# SCH_ESP32-v1_2025-11-17.net
KiCad netlist of a schematic drawn in EasyEDA
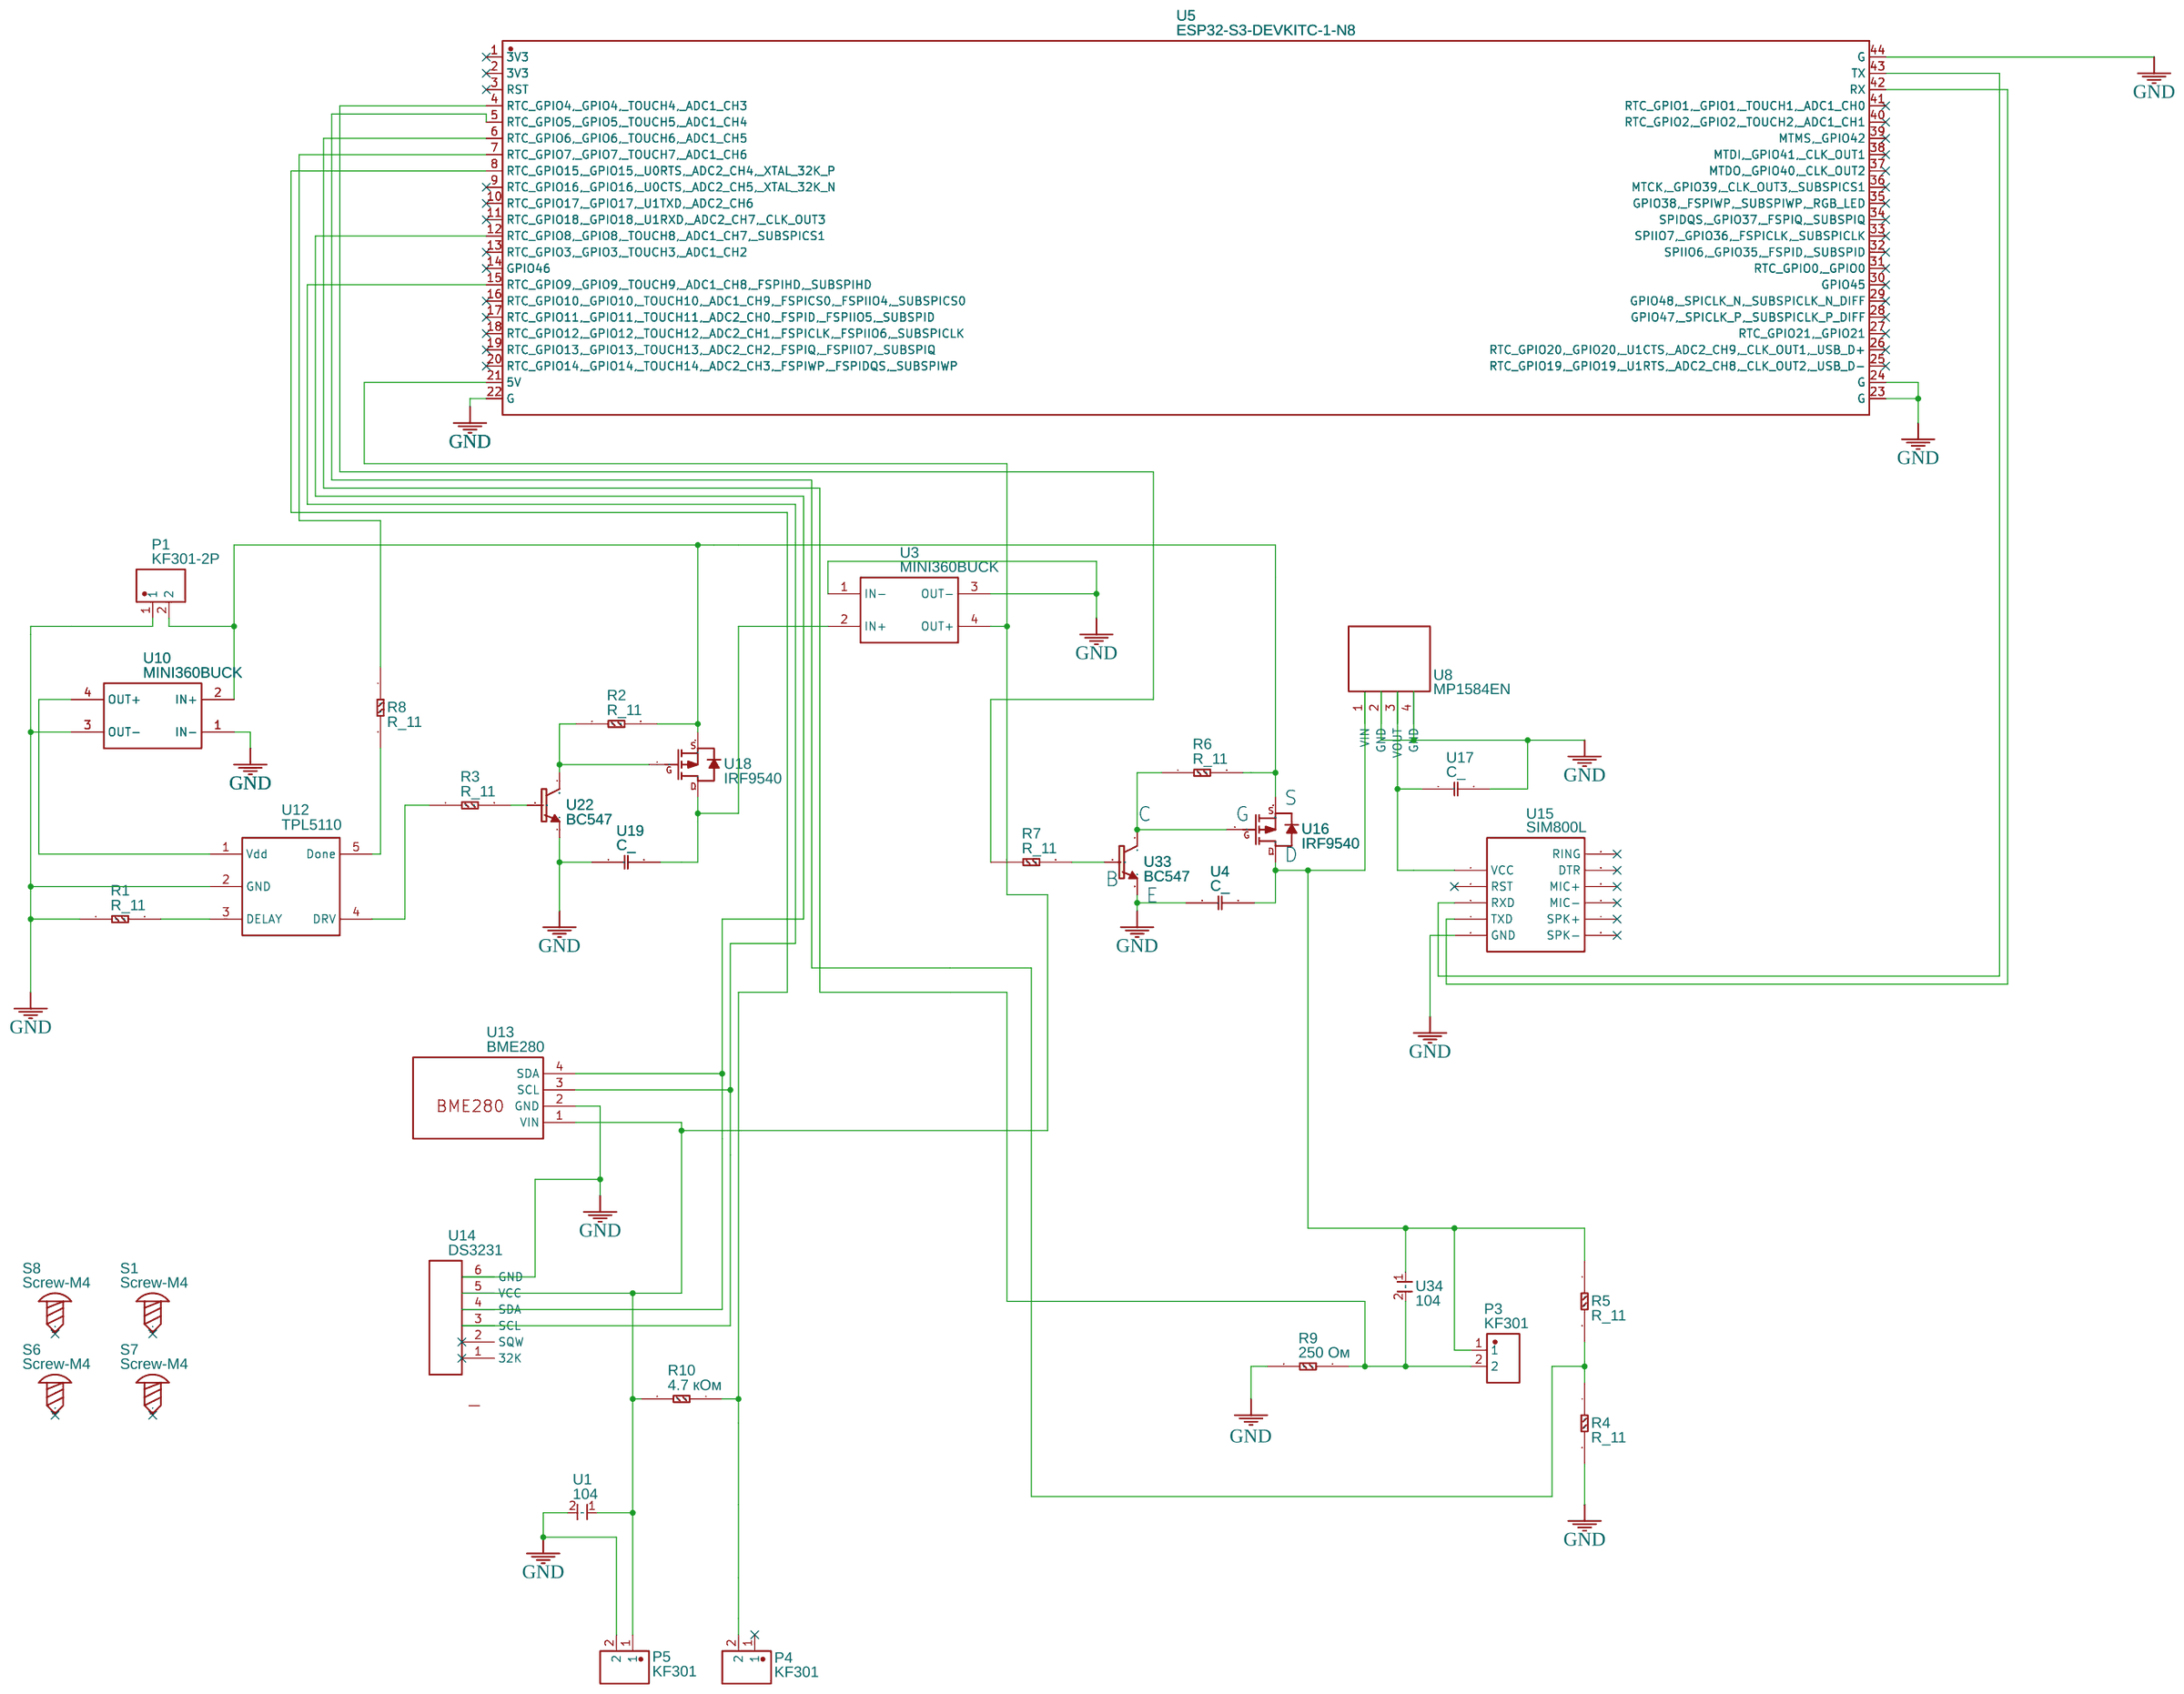
[diagram p0: schematic sheet]

(export (version "E")
  (design (tool "Eeschema 10.0.6"))
  (components
    (comp (ref "P1")
      (value "KF301-2P")
      (fields (field (name "Manufacturer Part") "KF301-2P接线端子"))
      (libsource (lib "") (part "KF301-2P VCC Y GND_1"))
    )
    (comp (ref "P3")
      (value "KF301")
      (fields (field (name "Manufacturer Part") "KF301-2P接线端子"))
      (libsource (lib "") (part "KF301-2P VCC Y GND_2"))
    )
    (comp (ref "P4")
      (value "KF301")
      (fields (field (name "Manufacturer Part") "KF301-2P接线端子"))
      (libsource (lib "") (part "KF301-2P VCC Y GND"))
    )
    (comp (ref "P5")
      (value "KF301")
      (fields (field (name "Manufacturer Part") "KF301-2P接线端子"))
      (libsource (lib "") (part "KF301-2P VCC Y GND"))
    )
    (comp (ref "R1") (value "R_11") (libsource (lib "") (part "R_")))
    (comp (ref "R2") (value "R_11") (libsource (lib "") (part "R_")))
    (comp (ref "R3") (value "R_11") (libsource (lib "") (part "R_")))
    (comp (ref "R4") (value "R_11") (libsource (lib "") (part "R__2")))
    (comp (ref "R5") (value "R_11") (libsource (lib "") (part "R__2")))
    (comp (ref "R6") (value "R_11") (libsource (lib "") (part "R_")))
    (comp (ref "R7") (value "R_11") (libsource (lib "") (part "R_")))
    (comp (ref "R8") (value "R_11") (libsource (lib "") (part "R__2")))
    (comp (ref "R9") (value "250 Ом") (libsource (lib "") (part "R__1")))
    (comp (ref "R10") (value "4.7 кОм") (libsource (lib "") (part "R__1")))
    (comp (ref "S1") (value "Screw-M4") (libsource (lib "") (part "Screw-M4")))
    (comp (ref "S6") (value "Screw-M4") (libsource (lib "") (part "Screw-M4")))
    (comp (ref "S7") (value "Screw-M4") (libsource (lib "") (part "Screw-M4")))
    (comp (ref "S8") (value "Screw-M4") (libsource (lib "") (part "Screw-M4")))
    (comp (ref "U1")
      (value "104")
      (fields (field (name "Manufacturer") "Fe"))
      (libsource (lib "") (part "104"))
    )
    (comp (ref "U3")
      (value "MINI360BUCK")
      (fields (field (name "Manufacturer Part") "Mini360"))
      (libsource (lib "") (part "MINI360BUCK_1"))
    )
    (comp (ref "U4") (value "C_") (libsource (lib "") (part "C_")))
    (comp (ref "U5")
      (value "ESP32-S3-DEVKITC-1-N8")
      (fields (field (name "Manufacturer") "ESPRESSIF(乐鑫)"))
      (libsource (lib "") (part "ESP32-S3-DEVKITC-1-N8"))
    )
    (comp (ref "U8") (value "MP1584EN") (libsource (lib "") (part "MP1584EN")))
    (comp (ref "U10")
      (value "MINI360BUCK")
      (fields (field (name "Manufacturer Part") "Mini360"))
      (libsource (lib "") (part "MINI360BUCK"))
    )
    (comp (ref "U12")
      (value "TPL5110")
      (fields (field (name "Manufacturer Part") "3435"))
      (libsource (lib "") (part "ADAFRUIT TPL5110 BREAKOUT"))
    )
    (comp (ref "U13") (value "BME280") (libsource (lib "") (part "BME280")))
    (comp (ref "U14") (value "DS3231") (libsource (lib "") (part "DS3231 upright")))
    (comp (ref "U15") (value "SIM800L") (libsource (lib "") (part "SIM800L")))
    (comp (ref "U16") (value "IRF9540") (libsource (lib "") (part "IRF9540")))
    (comp (ref "U17") (value "C_") (libsource (lib "") (part "C_")))
    (comp (ref "U18") (value "IRF9540") (libsource (lib "") (part "IRF9540")))
    (comp (ref "U19") (value "C_") (libsource (lib "") (part "C_")))
    (comp (ref "U22") (value "BC547") (libsource (lib "") (part "BC547")))
    (comp (ref "U33") (value "BC547") (libsource (lib "") (part "BC547")))
    (comp (ref "U34")
      (value "104")
      (fields (field (name "Manufacturer") "Fe"))
      (libsource (lib "") (part "104_1"))
    )
  )
  (nets
    (net (code "1") (name "GND") (class "Default")
      (node (ref "P1") (pin "1") (pinfunction "1_1") (pintype "unspecified"))
      (node (ref "P5") (pin "2") (pinfunction "2_2") (pintype "unspecified"))
      (node (ref "R1") (pin "1") (pinfunction "1_1") (pintype "unspecified"))
      (node (ref "R4") (pin "2") (pinfunction "2_2") (pintype "unspecified"))
      (node (ref "R9") (pin "2") (pinfunction "2_2") (pintype "unspecified"))
      (node (ref "U1") (pin "2") (pinfunction "2_2") (pintype "unspecified"))
      (node (ref "U10") (pin "1") (pinfunction "IN-_1") (pintype "unspecified"))
      (node (ref "U10") (pin "3") (pinfunction "OUT-_3") (pintype "unspecified"))
      (node (ref "U12") (pin "2") (pinfunction "GND_2") (pintype "unspecified"))
      (node (ref "U13") (pin "2") (pinfunction "GND_2") (pintype "unspecified"))
      (node (ref "U14") (pin "6") (pinfunction "GND_6") (pintype "unspecified"))
      (node (ref "U15") (pin "5") (pinfunction "GND_5") (pintype "unspecified"))
      (node (ref "U17") (pin "2") (pinfunction "2_2") (pintype "unspecified"))
      (node (ref "U19") (pin "1") (pinfunction "1_1") (pintype "unspecified"))
      (node (ref "U22") (pin "3") (pinfunction "E_3") (pintype "unspecified"))
      (node (ref "U3") (pin "1") (pinfunction "IN-_1") (pintype "unspecified"))
      (node (ref "U3") (pin "3") (pinfunction "OUT-_3") (pintype "unspecified"))
      (node (ref "U33") (pin "3") (pinfunction "E_3") (pintype "unspecified"))
      (node (ref "U4") (pin "1") (pinfunction "1_1") (pintype "unspecified"))
      (node (ref "U5") (pin "22") (pinfunction "G_22") (pintype "unspecified"))
      (node (ref "U5") (pin "23") (pinfunction "G_23") (pintype "unspecified"))
      (node (ref "U5") (pin "24") (pinfunction "G_24") (pintype "unspecified"))
      (node (ref "U5") (pin "44") (pinfunction "G_44") (pintype "unspecified"))
      (node (ref "U8") (pin "2") (pinfunction "GND_2") (pintype "unspecified"))
      (node (ref "U8") (pin "4") (pinfunction "GND_4") (pintype "unspecified"))
    )
    (net (code "2") (name "Net-(U5-RTC_GPIO4,_GPIO4,_TOUCH4,_ADC1_CH3)") (class "Default")
      (node (ref "R7") (pin "1") (pinfunction "1_1") (pintype "unspecified"))
      (node (ref "U5") (pin "4") (pinfunction "RTC_GPIO4,_GPIO4,_TOUCH4,_ADC1_CH3_4") (pintype "unspecified"))
    )
    (net (code "3") (name "Net-(U5-RTC_GPIO5,_GPIO5,_TOUCH5,_ADC1_CH4)") (class "Default")
      (node (ref "R4") (pin "1") (pinfunction "1_1") (pintype "unspecified"))
      (node (ref "R5") (pin "2") (pinfunction "2_2") (pintype "unspecified"))
      (node (ref "U5") (pin "5") (pinfunction "RTC_GPIO5,_GPIO5,_TOUCH5,_ADC1_CH4_5") (pintype "unspecified"))
    )
    (net (code "4") (name "Net-(U5-RTC_GPIO6,_GPIO6,_TOUCH6,_ADC1_CH5)") (class "Default")
      (node (ref "P3") (pin "2") (pinfunction "2_2") (pintype "unspecified"))
      (node (ref "R9") (pin "1") (pinfunction "1_1") (pintype "unspecified"))
      (node (ref "U34") (pin "2") (pinfunction "2_2") (pintype "unspecified"))
      (node (ref "U5") (pin "6") (pinfunction "RTC_GPIO6,_GPIO6,_TOUCH6,_ADC1_CH5_6") (pintype "unspecified"))
    )
    (net (code "5") (name "Net-(U5-RTC_GPIO7,_GPIO7,_TOUCH7,_ADC1_CH6)") (class "Default")
      (node (ref "R8") (pin "1") (pinfunction "1_1") (pintype "unspecified"))
      (node (ref "U5") (pin "7") (pinfunction "RTC_GPIO7,_GPIO7,_TOUCH7,_ADC1_CH6_7") (pintype "unspecified"))
    )
    (net (code "6") (name "Net-(U5-RTC_GPIO15,_GPIO15,_U0RTS,_ADC2_CH4,_XTAL_32K_P)") (class "Default")
      (node (ref "P4") (pin "2") (pinfunction "2_2") (pintype "unspecified"))
      (node (ref "R10") (pin "1") (pinfunction "1_1") (pintype "unspecified"))
      (node (ref "U5") (pin "8") (pinfunction "RTC_GPIO15,_GPIO15,_U0RTS,_ADC2_CH4,_XTAL_32K_P_8") (pintype "unspecified"))
    )
    (net (code "7") (name "Net-(U10-IN+)") (class "Default")
      (node (ref "P1") (pin "2") (pinfunction "2_2") (pintype "unspecified"))
      (node (ref "R2") (pin "2") (pinfunction "2_2") (pintype "unspecified"))
      (node (ref "R6") (pin "2") (pinfunction "2_2") (pintype "unspecified"))
      (node (ref "U10") (pin "2") (pinfunction "IN+_2") (pintype "unspecified"))
      (node (ref "U16") (pin "3") (pinfunction "S_3") (pintype "unspecified"))
      (node (ref "U18") (pin "3") (pinfunction "S_3") (pintype "unspecified"))
    )
    (net (code "8") (name "Net-(U10-OUT+)") (class "Default")
      (node (ref "U10") (pin "4") (pinfunction "OUT+_4") (pintype "unspecified"))
      (node (ref "U12") (pin "1") (pinfunction "Vdd_1") (pintype "unspecified"))
    )
    (net (code "9") (name "Net-(U12-DELAY)") (class "Default")
      (node (ref "R1") (pin "2") (pinfunction "2_2") (pintype "unspecified"))
      (node (ref "U12") (pin "3") (pinfunction "DELAY_3") (pintype "unspecified"))
    )
    (net (code "10") (name "Net-(U12-DRV)") (class "Default")
      (node (ref "R3") (pin "1") (pinfunction "1_1") (pintype "unspecified"))
      (node (ref "U12") (pin "4") (pinfunction "DRV_4") (pintype "unspecified"))
    )
    (net (code "11") (name "Net-(U12-Done)") (class "Default")
      (node (ref "R8") (pin "2") (pinfunction "2_2") (pintype "unspecified"))
      (node (ref "U12") (pin "5") (pinfunction "Done_5") (pintype "unspecified"))
    )
    (net (code "12") (name "Net-(U13-SCL)") (class "Default")
      (node (ref "U13") (pin "3") (pinfunction "SCL_3") (pintype "unspecified"))
      (node (ref "U14") (pin "3") (pinfunction "SCL_3") (pintype "unspecified"))
      (node (ref "U5") (pin "15") (pinfunction "RTC_GPIO9,_GPIO9,_TOUCH9,_ADC1_CH8,_FSPIHD,_SUBSPIHD_15") (pintype "unspecified"))
    )
    (net (code "13") (name "Net-(U13-SDA)") (class "Default")
      (node (ref "U13") (pin "4") (pinfunction "SDA_4") (pintype "unspecified"))
      (node (ref "U14") (pin "4") (pinfunction "SDA_4") (pintype "unspecified"))
      (node (ref "U5") (pin "12") (pinfunction "RTC_GPIO8,_GPIO8,_TOUCH8,_ADC1_CH7,_SUBSPICS1_12") (pintype "unspecified"))
    )
    (net (code "14") (name "Net-(U13-VIN)") (class "Default")
      (node (ref "P5") (pin "1") (pinfunction "1_1") (pintype "unspecified"))
      (node (ref "R10") (pin "2") (pinfunction "2_2") (pintype "unspecified"))
      (node (ref "U1") (pin "1") (pinfunction "1_1") (pintype "unspecified"))
      (node (ref "U13") (pin "1") (pinfunction "VIN_1") (pintype "unspecified"))
      (node (ref "U14") (pin "5") (pinfunction "VCC_5") (pintype "unspecified"))
      (node (ref "U3") (pin "4") (pinfunction "OUT+_4") (pintype "unspecified"))
      (node (ref "U5") (pin "21") (pinfunction "5V_21") (pintype "unspecified"))
    )
    (net (code "15") (name "Net-(U15-RXD)") (class "Default")
      (node (ref "U15") (pin "3") (pinfunction "RXD_3") (pintype "unspecified"))
      (node (ref "U5") (pin "43") (pinfunction "TX_43") (pintype "unspecified"))
    )
    (net (code "16") (name "Net-(U15-TXD)") (class "Default")
      (node (ref "U15") (pin "4") (pinfunction "TXD_4") (pintype "unspecified"))
      (node (ref "U5") (pin "42") (pinfunction "RX_42") (pintype "unspecified"))
    )
    (net (code "17") (name "Net-(U15-VCC)") (class "Default")
      (node (ref "U15") (pin "1") (pinfunction "VCC_1") (pintype "unspecified"))
      (node (ref "U17") (pin "1") (pinfunction "1_1") (pintype "unspecified"))
      (node (ref "U8") (pin "3") (pinfunction "VOUT_3") (pintype "unspecified"))
    )
    (net (code "18") (name "Net-(U16-D)") (class "Default")
      (node (ref "P3") (pin "1") (pinfunction "1_1") (pintype "unspecified"))
      (node (ref "R5") (pin "1") (pinfunction "1_1") (pintype "unspecified"))
      (node (ref "U16") (pin "2") (pinfunction "D_2") (pintype "unspecified"))
      (node (ref "U34") (pin "1") (pinfunction "1_1") (pintype "unspecified"))
      (node (ref "U4") (pin "2") (pinfunction "2_2") (pintype "unspecified"))
      (node (ref "U8") (pin "1") (pinfunction "VIN_1") (pintype "unspecified"))
    )
    (net (code "19") (name "Net-(U16-G)") (class "Default")
      (node (ref "R6") (pin "1") (pinfunction "1_1") (pintype "unspecified"))
      (node (ref "U16") (pin "1") (pinfunction "G_1") (pintype "unspecified"))
      (node (ref "U33") (pin "1") (pinfunction "C_1") (pintype "unspecified"))
    )
    (net (code "20") (name "Net-(U18-D)") (class "Default")
      (node (ref "U18") (pin "2") (pinfunction "D_2") (pintype "unspecified"))
      (node (ref "U19") (pin "2") (pinfunction "2_2") (pintype "unspecified"))
      (node (ref "U3") (pin "2") (pinfunction "IN+_2") (pintype "unspecified"))
    )
    (net (code "21") (name "Net-(U18-G)") (class "Default")
      (node (ref "R2") (pin "1") (pinfunction "1_1") (pintype "unspecified"))
      (node (ref "U18") (pin "1") (pinfunction "G_1") (pintype "unspecified"))
      (node (ref "U22") (pin "1") (pinfunction "C_1") (pintype "unspecified"))
    )
    (net (code "22") (name "Net-(U22-B)") (class "Default")
      (node (ref "R3") (pin "2") (pinfunction "2_2") (pintype "unspecified"))
      (node (ref "U22") (pin "2") (pinfunction "B_2") (pintype "unspecified"))
    )
    (net (code "23") (name "Net-(U33-B)") (class "Default")
      (node (ref "R7") (pin "2") (pinfunction "2_2") (pintype "unspecified"))
      (node (ref "U33") (pin "2") (pinfunction "B_2") (pintype "unspecified"))
    )
    (net (code "24") (name "unconnected-(P4-Pad1)") (class "Default")
      (node (ref "P4") (pin "1") (pinfunction "1_1") (pintype "unspecified+no_connect"))
    )
    (net (code "25") (name "unconnected-(S1-Pad1)") (class "Default")
      (node (ref "S1") (pin "1") (pinfunction "1_1") (pintype "unspecified+no_connect"))
    )
    (net (code "26") (name "unconnected-(S6-Pad1)") (class "Default")
      (node (ref "S6") (pin "1") (pinfunction "1_1") (pintype "unspecified+no_connect"))
    )
    (net (code "27") (name "unconnected-(S7-Pad1)") (class "Default")
      (node (ref "S7") (pin "1") (pinfunction "1_1") (pintype "unspecified+no_connect"))
    )
    (net (code "28") (name "unconnected-(S8-Pad1)") (class "Default")
      (node (ref "S8") (pin "1") (pinfunction "1_1") (pintype "unspecified+no_connect"))
    )
    (net (code "29") (name "unconnected-(U5-3V3-Pad1)") (class "Default")
      (node (ref "U5") (pin "1") (pinfunction "3V3_1") (pintype "unspecified+no_connect"))
    )
    (net (code "30") (name "unconnected-(U5-3V3-Pad2)") (class "Default")
      (node (ref "U5") (pin "2") (pinfunction "3V3_2") (pintype "unspecified+no_connect"))
    )
    (net (code "31") (name "unconnected-(U5-GPIO38,_FSPIWP,_SUBSPIWP,_RGB_LED-Pad35)") (class "Default")
      (node (ref "U5") (pin "35") (pinfunction "GPIO38,_FSPIWP,_SUBSPIWP,_RGB_LED_35") (pintype "unspecified+no_connect"))
    )
    (net (code "32") (name "unconnected-(U5-GPIO45-Pad30)") (class "Default")
      (node (ref "U5") (pin "30") (pinfunction "GPIO45_30") (pintype "unspecified+no_connect"))
    )
    (net (code "33") (name "unconnected-(U5-GPIO46-Pad14)") (class "Default")
      (node (ref "U5") (pin "14") (pinfunction "GPIO46_14") (pintype "unspecified+no_connect"))
    )
    (net (code "34") (name "unconnected-(U5-GPIO47,_SPICLK_P,_SUBSPICLK_P_DIFF-Pad28)") (class "Default")
      (node (ref "U5") (pin "28") (pinfunction "GPIO47,_SPICLK_P,_SUBSPICLK_P_DIFF_28") (pintype "unspecified+no_connect"))
    )
    (net (code "35") (name "unconnected-(U5-GPIO48,_SPICLK_N,_SUBSPICLK_N_DIFF-Pad29)") (class "Default")
      (node (ref "U5") (pin "29") (pinfunction "GPIO48,_SPICLK_N,_SUBSPICLK_N_DIFF_29") (pintype "unspecified+no_connect"))
    )
    (net (code "36") (name "unconnected-(U5-MTCK,_GPIO39,_CLK_OUT3,_SUBSPICS1-Pad36)") (class "Default")
      (node (ref "U5") (pin "36") (pinfunction "MTCK,_GPIO39,_CLK_OUT3,_SUBSPICS1_36") (pintype "unspecified+no_connect"))
    )
    (net (code "37") (name "unconnected-(U5-MTDI,_GPIO41,_CLK_OUT1-Pad38)") (class "Default")
      (node (ref "U5") (pin "38") (pinfunction "MTDI,_GPIO41,_CLK_OUT1_38") (pintype "unspecified+no_connect"))
    )
    (net (code "38") (name "unconnected-(U5-MTDO,_GPIO40,_CLK_OUT2-Pad37)") (class "Default")
      (node (ref "U5") (pin "37") (pinfunction "MTDO,_GPIO40,_CLK_OUT2_37") (pintype "unspecified+no_connect"))
    )
    (net (code "39") (name "unconnected-(U5-MTMS,_GPIO42-Pad39)") (class "Default")
      (node (ref "U5") (pin "39") (pinfunction "MTMS,_GPIO42_39") (pintype "unspecified+no_connect"))
    )
    (net (code "40") (name "unconnected-(U5-RST-Pad3)") (class "Default")
      (node (ref "U5") (pin "3") (pinfunction "RST_3") (pintype "unspecified+no_connect"))
    )
    (net (code "41") (name "unconnected-(U5-RTC_GPIO0,_GPIO0-Pad31)") (class "Default")
      (node (ref "U5") (pin "31") (pinfunction "RTC_GPIO0,_GPIO0_31") (pintype "unspecified+no_connect"))
    )
    (net (code "42") (name "unconnected-(U5-RTC_GPIO1,_GPIO1,_TOUCH1,_ADC1_CH0-Pad41)") (class "Default")
      (node (ref "U5") (pin "41") (pinfunction "RTC_GPIO1,_GPIO1,_TOUCH1,_ADC1_CH0_41") (pintype "unspecified+no_connect"))
    )
    (net (code "43") (name "unconnected-(U5-RTC_GPIO2,_GPIO2,_TOUCH2,_ADC1_CH1-Pad40)") (class "Default")
      (node (ref "U5") (pin "40") (pinfunction "RTC_GPIO2,_GPIO2,_TOUCH2,_ADC1_CH1_40") (pintype "unspecified+no_connect"))
    )
    (net (code "44") (name "unconnected-(U5-RTC_GPIO3,_GPIO3,_TOUCH3,_ADC1_CH2-Pad13)") (class "Default")
      (node (ref "U5") (pin "13") (pinfunction "RTC_GPIO3,_GPIO3,_TOUCH3,_ADC1_CH2_13") (pintype "unspecified+no_connect"))
    )
    (net (code "45") (name "unconnected-(U5-RTC_GPIO10,_GPIO10,_TOUCH10,_ADC1_CH9,_FSPICS0,_FSPIIO4,_SUBSPICS0-Pad16)") (class "Default")
      (node (ref "U5") (pin "16") (pinfunction "RTC_GPIO10,_GPIO10,_TOUCH10,_ADC1_CH9,_FSPICS0,_FSPIIO4,_SUBSPICS0_16") (pintype "unspecified+no_connect"))
    )
    (net (code "46") (name "unconnected-(U5-RTC_GPIO11,_GPIO11,_TOUCH11,_ADC2_CH0,_FSPID,_FSPIIO5,_SUBSPID-Pad17)") (class "Default")
      (node (ref "U5") (pin "17") (pinfunction "RTC_GPIO11,_GPIO11,_TOUCH11,_ADC2_CH0,_FSPID,_FSPIIO5,_SUBSPID_17") (pintype "unspecified+no_connect"))
    )
    (net (code "47") (name "unconnected-(U5-RTC_GPIO12,_GPIO12,_TOUCH12,_ADC2_CH1,_FSPICLK,_FSPIIO6,_SUBSPICLK-Pad18)") (class "Default")
      (node (ref "U5") (pin "18") (pinfunction "RTC_GPIO12,_GPIO12,_TOUCH12,_ADC2_CH1,_FSPICLK,_FSPIIO6,_SUBSPICLK_18") (pintype "unspecified+no_connect"))
    )
    (net (code "48") (name "unconnected-(U5-RTC_GPIO13,_GPIO13,_TOUCH13,_ADC2_CH2,_FSPIQ,_FSPIIO7,_SUBSPIQ-Pad19)") (class "Default")
      (node (ref "U5") (pin "19") (pinfunction "RTC_GPIO13,_GPIO13,_TOUCH13,_ADC2_CH2,_FSPIQ,_FSPIIO7,_SUBSPIQ_19") (pintype "unspecified+no_connect"))
    )
    (net (code "49") (name "unconnected-(U5-RTC_GPIO14,_GPIO14,_TOUCH14,_ADC2_CH3,_FSPIWP,_FSPIDQS,_SUBSPIWP-Pad20)") (class "Default")
      (node (ref "U5") (pin "20") (pinfunction "RTC_GPIO14,_GPIO14,_TOUCH14,_ADC2_CH3,_FSPIWP,_FSPIDQS,_SUBSPIWP_20") (pintype "unspecified+no_connect"))
    )
    (net (code "50") (name "unconnected-(U5-RTC_GPIO16,_GPIO16,_U0CTS,_ADC2_CH5,_XTAL_32K_N-Pad9)") (class "Default")
      (node (ref "U5") (pin "9") (pinfunction "RTC_GPIO16,_GPIO16,_U0CTS,_ADC2_CH5,_XTAL_32K_N_9") (pintype "unspecified+no_connect"))
    )
    (net (code "51") (name "unconnected-(U5-RTC_GPIO17,_GPIO17,_U1TXD,_ADC2_CH6-Pad10)") (class "Default")
      (node (ref "U5") (pin "10") (pinfunction "RTC_GPIO17,_GPIO17,_U1TXD,_ADC2_CH6_10") (pintype "unspecified+no_connect"))
    )
    (net (code "52") (name "unconnected-(U5-RTC_GPIO18,_GPIO18,_U1RXD,_ADC2_CH7,_CLK_OUT3-Pad11)") (class "Default")
      (node (ref "U5") (pin "11") (pinfunction "RTC_GPIO18,_GPIO18,_U1RXD,_ADC2_CH7,_CLK_OUT3_11") (pintype "unspecified+no_connect"))
    )
    (net (code "53") (name "unconnected-(U5-RTC_GPIO19,_GPIO19,_U1RTS,_ADC2_CH8,_CLK_OUT2,_USB_D--Pad25)") (class "Default")
      (node (ref "U5") (pin "25") (pinfunction "RTC_GPIO19,_GPIO19,_U1RTS,_ADC2_CH8,_CLK_OUT2,_USB_D-_25") (pintype "unspecified+no_connect"))
    )
    (net (code "54") (name "unconnected-(U5-RTC_GPIO20,_GPIO20,_U1CTS,_ADC2_CH9,_CLK_OUT1,_USB_D+-Pad26)") (class "Default")
      (node (ref "U5") (pin "26") (pinfunction "RTC_GPIO20,_GPIO20,_U1CTS,_ADC2_CH9,_CLK_OUT1,_USB_D+_26") (pintype "unspecified+no_connect"))
    )
    (net (code "55") (name "unconnected-(U5-RTC_GPIO21,_GPIO21-Pad27)") (class "Default")
      (node (ref "U5") (pin "27") (pinfunction "RTC_GPIO21,_GPIO21_27") (pintype "unspecified+no_connect"))
    )
    (net (code "56") (name "unconnected-(U5-SPIDQS,_GPIO37,_FSPIQ,_SUBSPIQ-Pad34)") (class "Default")
      (node (ref "U5") (pin "34") (pinfunction "SPIDQS,_GPIO37,_FSPIQ,_SUBSPIQ_34") (pintype "unspecified+no_connect"))
    )
    (net (code "57") (name "unconnected-(U5-SPIIO6,_GPIO35,_FSPID,_SUBSPID-Pad32)") (class "Default")
      (node (ref "U5") (pin "32") (pinfunction "SPIIO6,_GPIO35,_FSPID,_SUBSPID_32") (pintype "unspecified+no_connect"))
    )
    (net (code "58") (name "unconnected-(U5-SPIIO7,_GPIO36,_FSPICLK,_SUBSPICLK-Pad33)") (class "Default")
      (node (ref "U5") (pin "33") (pinfunction "SPIIO7,_GPIO36,_FSPICLK,_SUBSPICLK_33") (pintype "unspecified+no_connect"))
    )
    (net (code "59") (name "unconnected-(U14-32K-Pad1)") (class "Default")
      (node (ref "U14") (pin "1") (pinfunction "32K_1") (pintype "unspecified+no_connect"))
    )
    (net (code "60") (name "unconnected-(U14-SQW-Pad2)") (class "Default")
      (node (ref "U14") (pin "2") (pinfunction "SQW_2") (pintype "unspecified+no_connect"))
    )
    (net (code "61") (name "unconnected-(U15-DTR-Pad10)") (class "Default")
      (node (ref "U15") (pin "10") (pinfunction "DTR_10") (pintype "unspecified+no_connect"))
    )
    (net (code "62") (name "unconnected-(U15-MIC+-Pad9)") (class "Default")
      (node (ref "U15") (pin "9") (pinfunction "MIC+_9") (pintype "unspecified+no_connect"))
    )
    (net (code "63") (name "unconnected-(U15-MIC--Pad8)") (class "Default")
      (node (ref "U15") (pin "8") (pinfunction "MIC-_8") (pintype "unspecified+no_connect"))
    )
    (net (code "64") (name "unconnected-(U15-RING-Pad11)") (class "Default")
      (node (ref "U15") (pin "11") (pinfunction "RING_11") (pintype "unspecified+no_connect"))
    )
    (net (code "65") (name "unconnected-(U15-RST-Pad2)") (class "Default")
      (node (ref "U15") (pin "2") (pinfunction "RST_2") (pintype "unspecified+no_connect"))
    )
    (net (code "66") (name "unconnected-(U15-SPK+-Pad7)") (class "Default")
      (node (ref "U15") (pin "7") (pinfunction "SPK+_7") (pintype "unspecified+no_connect"))
    )
    (net (code "67") (name "unconnected-(U15-SPK--Pad6)") (class "Default")
      (node (ref "U15") (pin "6") (pinfunction "SPK-_6") (pintype "unspecified+no_connect"))
    )
  )
)
